# doodle_with_clock3_jump5.net
KiCad netlist of a schematic drawn in EAGLE
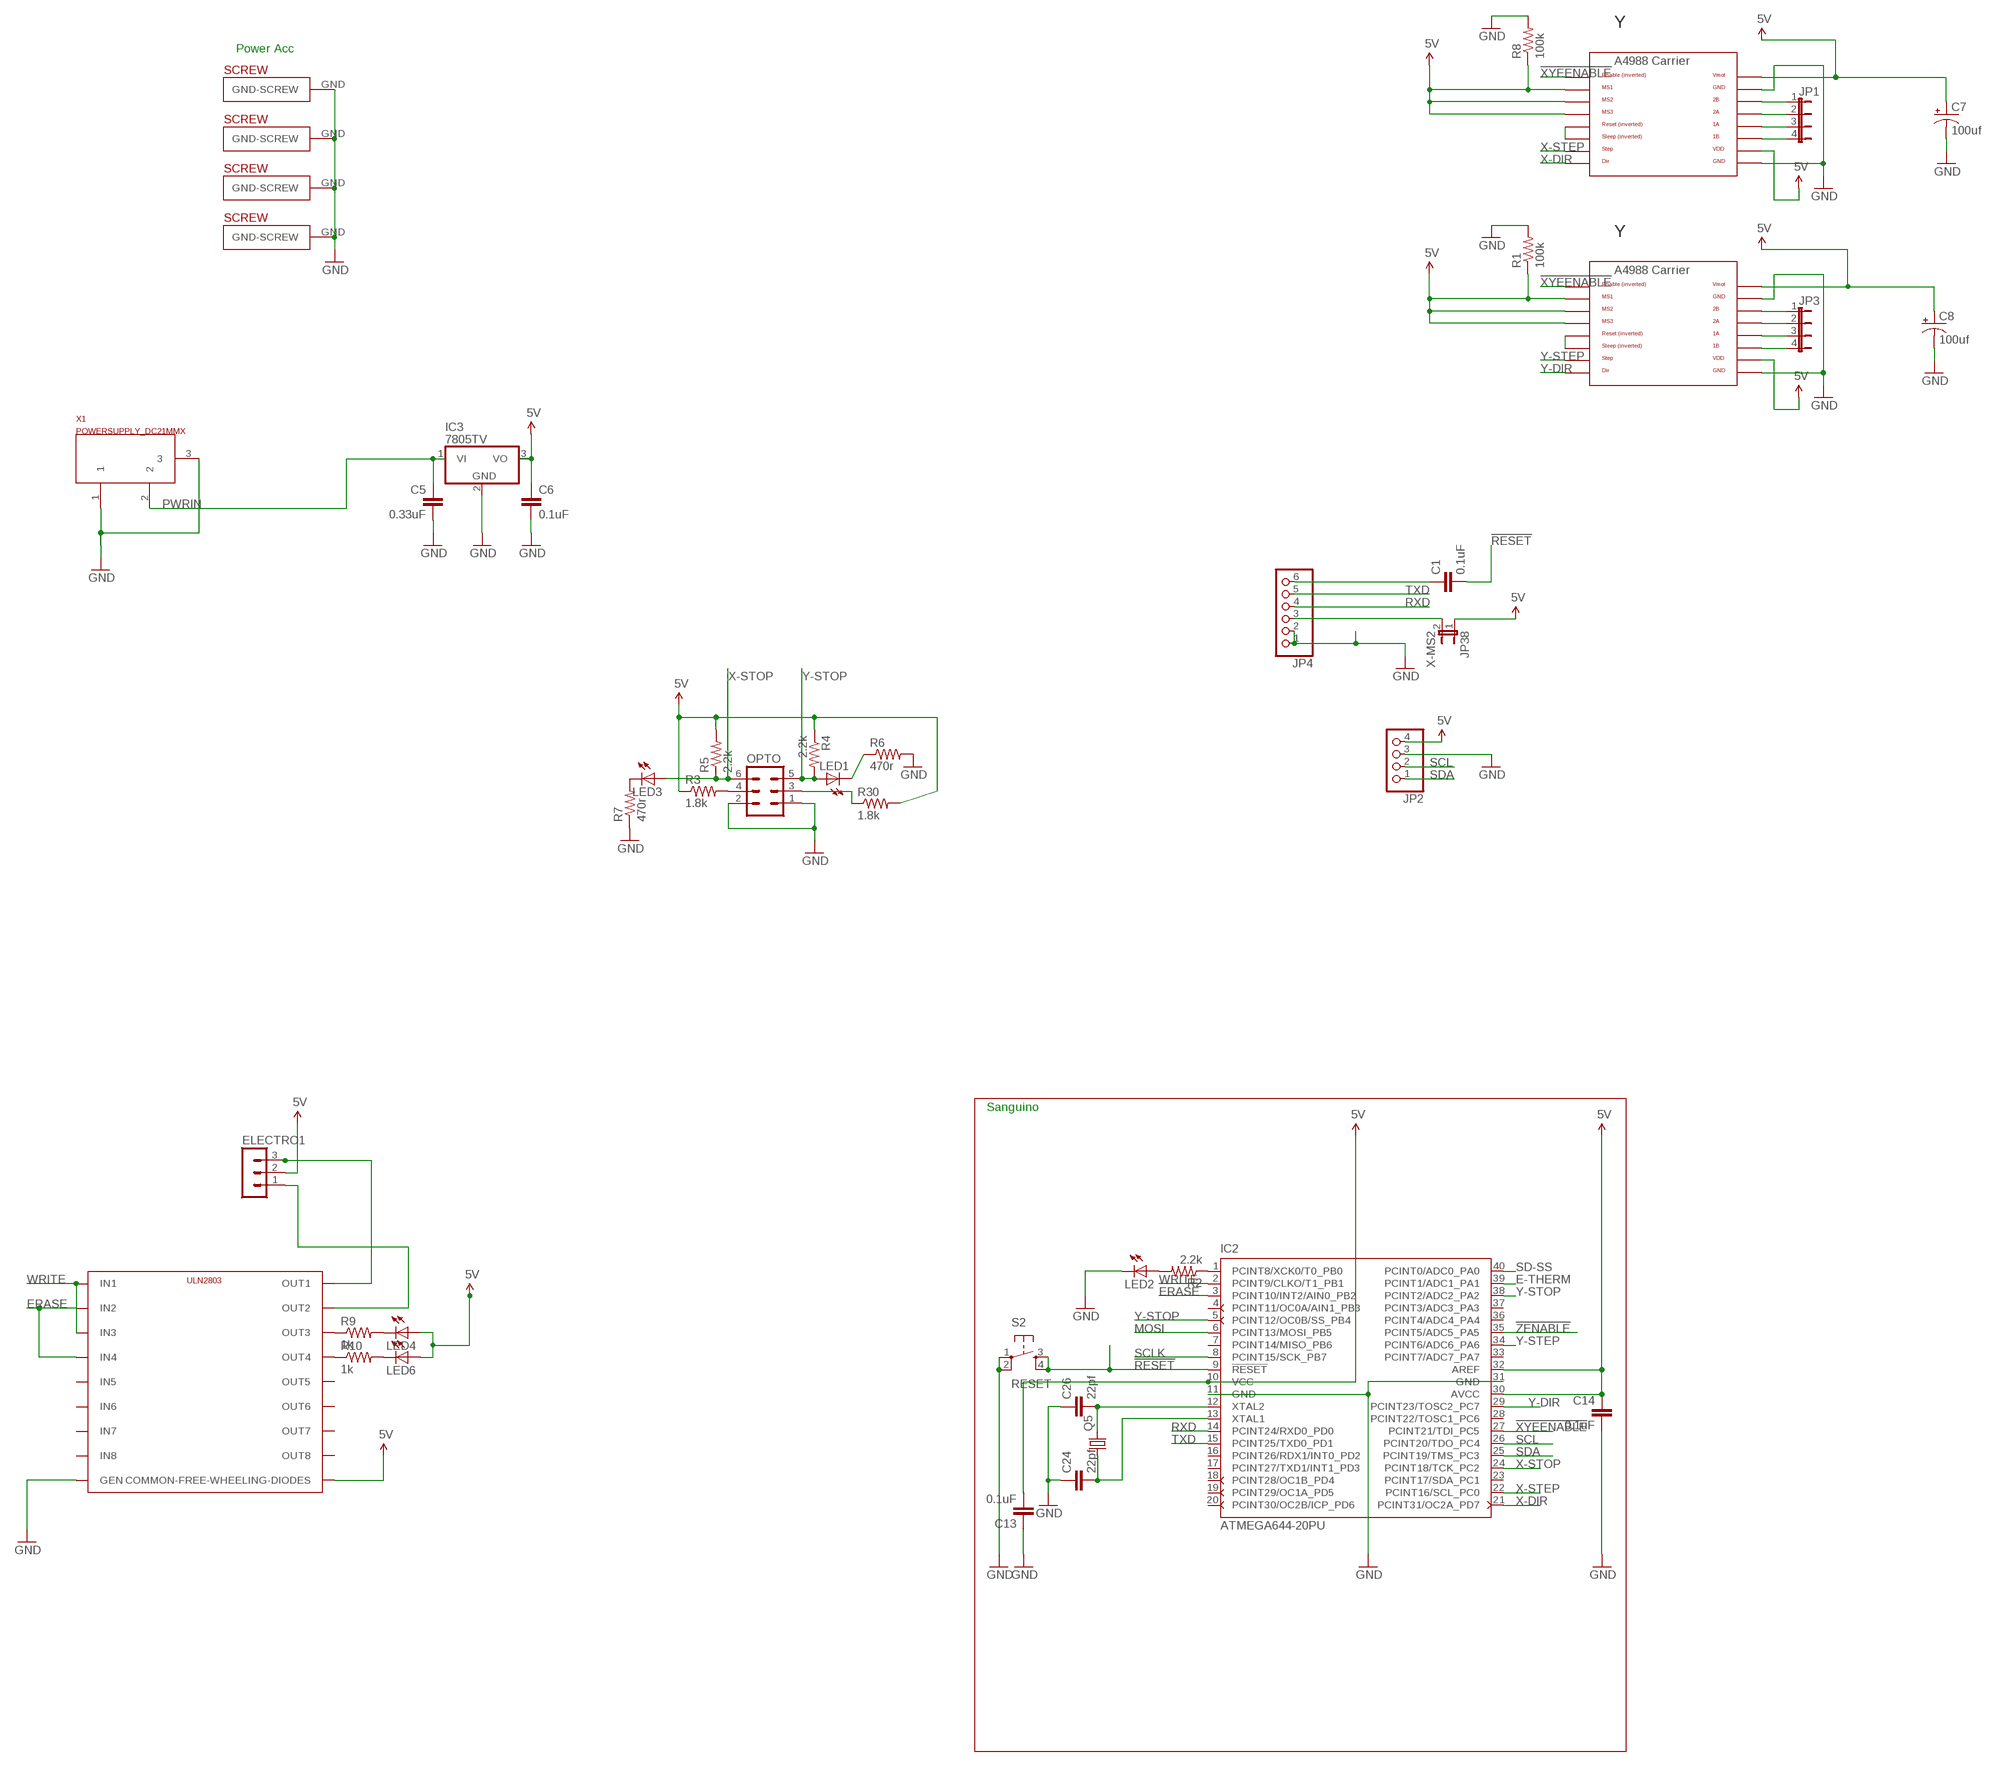
[diagram p0: schematic, sheet 1]

(export (version "E")
  (design (tool "Eeschema 10.0.6"))
  (components
    (comp (ref "C1")
      (value "0.1uF")
      (footprint "eagle-import:CAP-PTH-SMALL2")
      (libsource (lib "eagle-import") (part "CAPPTH2"))
    )
    (comp (ref "C5")
      (value "0.33uF")
      (footprint "eagle-import:CAP-PTH-SMALL2")
      (libsource (lib "eagle-import") (part "CAPPTH2"))
    )
    (comp (ref "C6")
      (value "0.1uF")
      (footprint "eagle-import:CAP-PTH-SMALL2")
      (libsource (lib "eagle-import") (part "CAPPTH2"))
    )
    (comp (ref "C7")
      (value "100uf")
      (footprint "eagle-import:CPOL-RADIAL-100UF-25V")
      (libsource (lib "eagle-import") (part "CAP_POLPTH1"))
    )
    (comp (ref "C8")
      (value "100uf")
      (footprint "eagle-import:CPOL-RADIAL-100UF-25V")
      (libsource (lib "eagle-import") (part "CAP_POLPTH1"))
    )
    (comp (ref "C13")
      (value "0.1uF")
      (footprint "eagle-import:CAP-PTH-SMALL2")
      (libsource (lib "eagle-import") (part "CAPPTH2"))
    )
    (comp (ref "C14")
      (value "0.1uF")
      (footprint "eagle-import:CAP-PTH-SMALL2")
      (libsource (lib "eagle-import") (part "CAPPTH2"))
    )
    (comp (ref "C24")
      (value "22pf")
      (footprint "eagle-import:CAP-PTH-SMALL2")
      (libsource (lib "eagle-import") (part "CAPPTH2"))
    )
    (comp (ref "C26")
      (value "22pf")
      (footprint "eagle-import:CAP-PTH-SMALL2")
      (libsource (lib "eagle-import") (part "CAPPTH2"))
    )
    (comp (ref "ELECTRO1")
      (value "MA03-1")
      (footprint "eagle-import:MA03-1")
      (libsource (lib "eagle-import") (part "MA03-1"))
    )
    (comp (ref "IC2")
      (value "ATMEGA644-20PU")
      (footprint "eagle-import:DIL40")
      (libsource (lib "eagle-import") (part "ATMEGA644-PU20"))
    )
    (comp (ref "IC3")
      (value "7805TV")
      (footprint "eagle-import:TO220V")
      (libsource (lib "eagle-import") (part "78TV05"))
    )
    (comp (ref "JP1")
      (value "JP4E")
      (footprint "eagle-import:JP4")
      (libsource (lib "eagle-import") (part "JP4E"))
    )
    (comp (ref "JP2")
      (value "PINHD-1X4")
      (footprint "eagle-import:1X04")
      (libsource (lib "eagle-import") (part "PINHD-1X4"))
    )
    (comp (ref "JP3")
      (value "JP4E")
      (footprint "eagle-import:JP4")
      (libsource (lib "eagle-import") (part "JP4E"))
    )
    (comp (ref "JP4")
      (value "PINHD-1X6/90")
      (footprint "eagle-import:1X06_90")
      (libsource (lib "eagle-import") (part "PINHD-1X6/90"))
    )
    (comp (ref "JP38")
      (value "X-MS2")
      (footprint "eagle-import:1X02")
      (libsource (lib "eagle-import") (part "JUMPER-2PTH"))
    )
    (comp (ref "LED1")
      (value "LED3MM")
      (footprint "eagle-import:LED3MM")
      (libsource (lib "eagle-import") (part "LED3MM"))
    )
    (comp (ref "LED2")
      (value "LED3MM")
      (footprint "eagle-import:LED3MM")
      (libsource (lib "eagle-import") (part "LED3MM"))
    )
    (comp (ref "LED3")
      (value "LED3MM")
      (footprint "eagle-import:LED3MM")
      (libsource (lib "eagle-import") (part "LED3MM"))
    )
    (comp (ref "LED4")
      (value "LED3MM")
      (footprint "eagle-import:LED3MM")
      (libsource (lib "eagle-import") (part "LED3MM"))
    )
    (comp (ref "LED6")
      (value "LED3MM")
      (footprint "eagle-import:LED3MM")
      (libsource (lib "eagle-import") (part "LED3MM"))
    )
    (comp (ref "OPTO")
      (value "MA03-2")
      (footprint "eagle-import:MA03-2")
      (libsource (lib "eagle-import") (part "MA03-2"))
    )
    (comp (ref "Q5")
      (value "CRYSTALHC49S")
      (footprint "eagle-import:HC49_S")
      (libsource (lib "eagle-import") (part "CRYSTALHC49S"))
    )
    (comp (ref "R1")
      (value "100k")
      (footprint "eagle-import:0207_7")
      (libsource (lib "eagle-import") (part "R-US_0207/7"))
    )
    (comp (ref "R2")
      (value "2.2k")
      (footprint "eagle-import:0207_2V")
      (libsource (lib "eagle-import") (part "resistor_R-US_0207/2V"))
    )
    (comp (ref "R3")
      (value "1.8k")
      (footprint "eagle-import:0207_2V")
      (libsource (lib "eagle-import") (part "resistor_R-US_0207/2V"))
    )
    (comp (ref "R4")
      (value "2.2k")
      (footprint "eagle-import:0207_2V")
      (libsource (lib "eagle-import") (part "resistor_R-US_0207/2V"))
    )
    (comp (ref "R5")
      (value "2.2k")
      (footprint "eagle-import:0207_2V")
      (libsource (lib "eagle-import") (part "resistor_R-US_0207/2V"))
    )
    (comp (ref "R6")
      (value "470r")
      (footprint "eagle-import:0207_2V")
      (libsource (lib "eagle-import") (part "resistor_R-US_0207/2V"))
    )
    (comp (ref "R7")
      (value "470r")
      (footprint "eagle-import:0207_2V")
      (libsource (lib "eagle-import") (part "resistor_R-US_0207/2V"))
    )
    (comp (ref "R8")
      (value "100k")
      (footprint "eagle-import:0207_7")
      (libsource (lib "eagle-import") (part "R-US_0207/7"))
    )
    (comp (ref "R9")
      (value "1k")
      (footprint "eagle-import:0207_2V")
      (libsource (lib "eagle-import") (part "resistor_R-US_0207/2V"))
    )
    (comp (ref "R10")
      (value "1k")
      (footprint "eagle-import:0207_2V")
      (libsource (lib "eagle-import") (part "resistor_R-US_0207/2V"))
    )
    (comp (ref "R30")
      (value "1.8k")
      (footprint "eagle-import:0207_2V")
      (libsource (lib "eagle-import") (part "resistor_R-US_0207/2V"))
    )
    (comp (ref "S2")
      (value "RESET")
      (footprint "eagle-import:TACTILE-PTH")
      (libsource (lib "eagle-import") (part "TAC_SWITCHPTH"))
    )
    (comp (ref "U$1")
      (value "A4988BREAKOUT")
      (footprint "eagle-import:A4988BREAKOUT")
      (libsource (lib "eagle-import") (part "A4988BREAKOUT"))
    )
    (comp (ref "U$2")
      (value "ULN2803")
      (footprint "eagle-import:P-DIP")
      (libsource (lib "eagle-import") (part "ULN2803"))
    )
    (comp (ref "U$7")
      (value "A4988BREAKOUT")
      (footprint "eagle-import:A4988BREAKOUT")
      (libsource (lib "eagle-import") (part "A4988BREAKOUT"))
    )
    (comp (ref "U$14")
      (value "PLATED-SCREW")
      (footprint "eagle-import:PLATEDSCREW")
      (libsource (lib "eagle-import") (part "PLATED-SCREW"))
    )
    (comp (ref "U$17")
      (value "PLATED-SCREW")
      (footprint "eagle-import:PLATEDSCREW")
      (libsource (lib "eagle-import") (part "PLATED-SCREW"))
    )
    (comp (ref "U$18")
      (value "PLATED-SCREW")
      (footprint "eagle-import:PLATEDSCREW")
      (libsource (lib "eagle-import") (part "PLATED-SCREW"))
    )
    (comp (ref "U$38")
      (value "PLATED-SCREW")
      (footprint "eagle-import:PLATEDSCREW")
      (libsource (lib "eagle-import") (part "PLATED-SCREW"))
    )
    (comp (ref "X1")
      (value "POWERSUPPLY_DC21MMX")
      (footprint "eagle-import:POWERSUPPLY_DC-21MM")
      (libsource (lib "eagle-import") (part "POWERSUPPLY_DC21MMX"))
    )
  )
  (nets
    (net (code "1") (name "/E-THERM") (class "Default")
      (node (ref "IC2") (pin "39") (pinfunction "PCINT1/ADC1_PA1_39") (pintype "bidirectional"))
    )
    (net (code "2") (name "/ERASE") (class "Default")
      (node (ref "IC2") (pin "3") (pinfunction "PCINT10/INT2/AIN0_PB2_3") (pintype "bidirectional"))
      (node (ref "U$2") (pin "IN2") (pinfunction "IN2_IN2") (pintype "input"))
      (node (ref "U$2") (pin "IN4") (pinfunction "IN4_IN4") (pintype "input"))
    )
    (net (code "3") (name "/MOSI") (class "Default")
      (node (ref "IC2") (pin "6") (pinfunction "PCINT13/MOSI_PB5_6") (pintype "bidirectional"))
    )
    (net (code "4") (name "/PWRIN") (class "Default")
      (node (ref "C5") (pin "1") (pinfunction "1_1") (pintype "passive"))
      (node (ref "IC3") (pin "1") (pinfunction "VI_1") (pintype "input"))
      (node (ref "X1") (pin "2") (pinfunction "2_2") (pintype "power_in"))
    )
    (net (code "5") (name "/RXD") (class "Default")
      (node (ref "IC2") (pin "14") (pinfunction "PCINT24/RXD0_PD0_14") (pintype "bidirectional"))
      (node (ref "JP4") (pin "4") (pinfunction "4_4") (pintype "passive"))
    )
    (net (code "6") (name "/SCL") (class "Default")
      (node (ref "IC2") (pin "26") (pinfunction "PCINT20/TDO_PC4_26") (pintype "bidirectional"))
      (node (ref "JP2") (pin "2") (pinfunction "2_2") (pintype "passive"))
    )
    (net (code "7") (name "/SCLK") (class "Default")
      (node (ref "IC2") (pin "8") (pinfunction "PCINT15/SCK_PB7_8") (pintype "bidirectional"))
    )
    (net (code "8") (name "/SD-SS") (class "Default")
      (node (ref "IC2") (pin "40") (pinfunction "PCINT0/ADC0_PA0_40") (pintype "bidirectional"))
    )
    (net (code "9") (name "/SDA") (class "Default")
      (node (ref "IC2") (pin "25") (pinfunction "PCINT19/TMS_PC3_25") (pintype "bidirectional"))
      (node (ref "JP2") (pin "1") (pinfunction "1_1") (pintype "passive"))
    )
    (net (code "10") (name "/TXD") (class "Default")
      (node (ref "IC2") (pin "15") (pinfunction "PCINT25/TXD0_PD1_15") (pintype "bidirectional"))
      (node (ref "JP4") (pin "5") (pinfunction "5_5") (pintype "passive"))
    )
    (net (code "11") (name "/WRITE") (class "Default")
      (node (ref "IC2") (pin "2") (pinfunction "PCINT9/CLKO/T1_PB1_2") (pintype "bidirectional"))
      (node (ref "U$2") (pin "IN1") (pinfunction "IN1_IN1") (pintype "input"))
      (node (ref "U$2") (pin "IN3") (pinfunction "IN3_IN3") (pintype "input"))
    )
    (net (code "12") (name "/X-DIR") (class "Default")
      (node (ref "IC2") (pin "21") (pinfunction "PCINT31/OC2A_PD7_21") (pintype "bidirectional"))
      (node (ref "U$7") (pin "DIR") (pinfunction "DIR_DIR") (pintype "input"))
    )
    (net (code "13") (name "/X-STEP") (class "Default")
      (node (ref "IC2") (pin "22") (pinfunction "PCINT16/SCL_PC0_22") (pintype "bidirectional"))
      (node (ref "U$7") (pin "STEP") (pinfunction "STEP_STEP") (pintype "input"))
    )
    (net (code "14") (name "/X-STOP") (class "Default")
      (node (ref "IC2") (pin "24") (pinfunction "PCINT18/TCK_PC2_24") (pintype "bidirectional"))
      (node (ref "LED3") (pin "A") (pinfunction "A_A") (pintype "passive"))
      (node (ref "OPTO") (pin "6") (pinfunction "6_6") (pintype "passive"))
      (node (ref "R5") (pin "1") (pinfunction "1_1") (pintype "passive"))
    )
    (net (code "15") (name "/Y-DIR") (class "Default")
      (node (ref "IC2") (pin "29") (pinfunction "PCINT23/TOSC2_PC7_29") (pintype "bidirectional"))
      (node (ref "U$1") (pin "DIR") (pinfunction "DIR_DIR") (pintype "input"))
    )
    (net (code "16") (name "/Y-STEP") (class "Default")
      (node (ref "IC2") (pin "34") (pinfunction "PCINT6/ADC6_PA6_34") (pintype "bidirectional"))
      (node (ref "U$1") (pin "STEP") (pinfunction "STEP_STEP") (pintype "input"))
    )
    (net (code "17") (name "/Y-STOP") (class "Default")
      (node (ref "IC2") (pin "38") (pinfunction "PCINT2/ADC2_PA2_38") (pintype "bidirectional"))
      (node (ref "IC2") (pin "5") (pinfunction "PCINT12/OC0B/SS_PB4_5") (pintype "bidirectional"))
      (node (ref "LED1") (pin "A") (pinfunction "A_A") (pintype "passive"))
      (node (ref "OPTO") (pin "5") (pinfunction "5_5") (pintype "passive"))
      (node (ref "R4") (pin "2") (pinfunction "2_2") (pintype "passive"))
    )
    (net (code "18") (name "/~{RESET}") (class "Default")
      (node (ref "C1") (pin "2") (pinfunction "2_2") (pintype "passive"))
      (node (ref "IC2") (pin "9") (pinfunction "~{RESET}_9") (pintype "input"))
      (node (ref "S2") (pin "3") (pinfunction "3_3") (pintype "passive"))
      (node (ref "S2") (pin "4") (pinfunction "4_4") (pintype "passive"))
    )
    (net (code "19") (name "/~{XYEENABLE}") (class "Default")
      (node (ref "IC2") (pin "27") (pinfunction "PCINT21/TDI_PC5_27") (pintype "bidirectional"))
      (node (ref "U$1") (pin "EN") (pinfunction "EN_EN") (pintype "input"))
      (node (ref "U$7") (pin "EN") (pinfunction "EN_EN") (pintype "input"))
    )
    (net (code "20") (name "/~{ZENABLE}") (class "Default")
      (node (ref "IC2") (pin "35") (pinfunction "PCINT5/ADC5_PA5_35") (pintype "bidirectional"))
    )
    (net (code "21") (name "5V") (class "Default")
      (node (ref "C13") (pin "2") (pinfunction "2_2") (pintype "passive"))
      (node (ref "C14") (pin "1") (pinfunction "1_1") (pintype "passive"))
      (node (ref "C6") (pin "1") (pinfunction "1_1") (pintype "passive"))
      (node (ref "C7") (pin "1") (pinfunction "+_1") (pintype "passive"))
      (node (ref "C8") (pin "1") (pinfunction "+_1") (pintype "passive"))
      (node (ref "ELECTRO1") (pin "2") (pinfunction "2_2") (pintype "passive"))
      (node (ref "IC2") (pin "10") (pinfunction "VCC_10") (pintype "power_in"))
      (node (ref "IC2") (pin "30") (pinfunction "AVCC_30") (pintype "power_in"))
      (node (ref "IC2") (pin "32") (pinfunction "AREF_32") (pintype "passive"))
      (node (ref "IC3") (pin "3") (pinfunction "VO_3") (pintype "passive"))
      (node (ref "JP2") (pin "4") (pinfunction "4_4") (pintype "passive"))
      (node (ref "JP38") (pin "1") (pinfunction "1_1") (pintype "passive"))
      (node (ref "LED4") (pin "A") (pinfunction "A_A") (pintype "passive"))
      (node (ref "LED6") (pin "A") (pinfunction "A_A") (pintype "passive"))
      (node (ref "R1") (pin "1") (pinfunction "1_1") (pintype "passive"))
      (node (ref "R3") (pin "1") (pinfunction "1_1") (pintype "passive"))
      (node (ref "R30") (pin "2") (pinfunction "2_2") (pintype "passive"))
      (node (ref "R4") (pin "1") (pinfunction "1_1") (pintype "passive"))
      (node (ref "R5") (pin "2") (pinfunction "2_2") (pintype "passive"))
      (node (ref "R8") (pin "1") (pinfunction "1_1") (pintype "passive"))
      (node (ref "U$1") (pin "MS1") (pinfunction "MS1_MS1") (pintype "input"))
      (node (ref "U$1") (pin "MS2") (pinfunction "MS2_MS2") (pintype "input"))
      (node (ref "U$1") (pin "MS3") (pinfunction "MS3_MS3") (pintype "input"))
      (node (ref "U$1") (pin "VDD") (pinfunction "VDD_VDD") (pintype "power_in"))
      (node (ref "U$1") (pin "VMOT") (pinfunction "VMOT_VMOT") (pintype "power_in"))
      (node (ref "U$2") (pin "COMMON-FREE-WHEELING-DIODES") (pinfunction "COMMON-FREE-WHEELING-DIODES_COMMON-FREE-WHEELING-DIODES") (pintype "output"))
      (node (ref "U$7") (pin "MS1") (pinfunction "MS1_MS1") (pintype "input"))
      (node (ref "U$7") (pin "MS2") (pinfunction "MS2_MS2") (pintype "input"))
      (node (ref "U$7") (pin "MS3") (pinfunction "MS3_MS3") (pintype "input"))
      (node (ref "U$7") (pin "VDD") (pinfunction "VDD_VDD") (pintype "power_in"))
      (node (ref "U$7") (pin "VMOT") (pinfunction "VMOT_VMOT") (pintype "power_in"))
    )
    (net (code "22") (name "GND") (class "Default")
      (node (ref "C13") (pin "1") (pinfunction "1_1") (pintype "passive"))
      (node (ref "C14") (pin "2") (pinfunction "2_2") (pintype "passive"))
      (node (ref "C24") (pin "1") (pinfunction "1_1") (pintype "passive"))
      (node (ref "C26") (pin "1") (pinfunction "1_1") (pintype "passive"))
      (node (ref "C5") (pin "2") (pinfunction "2_2") (pintype "passive"))
      (node (ref "C6") (pin "2") (pinfunction "2_2") (pintype "passive"))
      (node (ref "C7") (pin "2") (pinfunction "-_2") (pintype "passive"))
      (node (ref "C8") (pin "2") (pinfunction "-_2") (pintype "passive"))
      (node (ref "IC2") (pin "11") (pinfunction "GND_11") (pintype "power_in"))
      (node (ref "IC2") (pin "31") (pinfunction "GND_31") (pintype "power_in"))
      (node (ref "IC3") (pin "2") (pinfunction "GND_2") (pintype "passive"))
      (node (ref "JP2") (pin "3") (pinfunction "3_3") (pintype "passive"))
      (node (ref "JP4") (pin "1") (pinfunction "1_1") (pintype "passive"))
      (node (ref "JP4") (pin "2") (pinfunction "2_2") (pintype "passive"))
      (node (ref "LED2") (pin "K") (pinfunction "C_K") (pintype "passive"))
      (node (ref "OPTO") (pin "1") (pinfunction "1_1") (pintype "passive"))
      (node (ref "OPTO") (pin "2") (pinfunction "2_2") (pintype "passive"))
      (node (ref "R1") (pin "2") (pinfunction "2_2") (pintype "passive"))
      (node (ref "R6") (pin "2") (pinfunction "2_2") (pintype "passive"))
      (node (ref "R7") (pin "1") (pinfunction "1_1") (pintype "passive"))
      (node (ref "R8") (pin "2") (pinfunction "2_2") (pintype "passive"))
      (node (ref "S2") (pin "1") (pinfunction "1_1") (pintype "passive"))
      (node (ref "S2") (pin "2") (pinfunction "2_2") (pintype "passive"))
      (node (ref "U$1") (pin "GND") (pinfunction "GND_GND") (pintype "power_in"))
      (node (ref "U$1") (pin "GND@0") (pinfunction "GND_GND@0") (pintype "power_in"))
      (node (ref "U$14") (pin "GND") (pinfunction "GND-SCREW_GND") (pintype "bidirectional"))
      (node (ref "U$17") (pin "GND") (pinfunction "GND-SCREW_GND") (pintype "bidirectional"))
      (node (ref "U$18") (pin "GND") (pinfunction "GND-SCREW_GND") (pintype "bidirectional"))
      (node (ref "U$2") (pin "GEN") (pinfunction "GEN_GEN") (pintype "power_in"))
      (node (ref "U$38") (pin "GND") (pinfunction "GND-SCREW_GND") (pintype "bidirectional"))
      (node (ref "U$7") (pin "GND") (pinfunction "GND_GND") (pintype "power_in"))
      (node (ref "U$7") (pin "GND@0") (pinfunction "GND_GND@0") (pintype "power_in"))
      (node (ref "X1") (pin "1") (pinfunction "1_1") (pintype "power_in"))
      (node (ref "X1") (pin "3") (pinfunction "3_3") (pintype "power_in"))
    )
    (net (code "23") (name "Net-(C1-Pad1)") (class "Default")
      (node (ref "C1") (pin "1") (pinfunction "1_1") (pintype "passive"))
      (node (ref "JP4") (pin "6") (pinfunction "6_6") (pintype "passive"))
    )
    (net (code "24") (name "Net-(ELECTRO1-Pad1)") (class "Default")
      (node (ref "ELECTRO1") (pin "1") (pinfunction "1_1") (pintype "passive"))
      (node (ref "U$2") (pin "OUT2") (pinfunction "OUT2_OUT2") (pintype "output"))
    )
    (net (code "25") (name "Net-(ELECTRO1-Pad3)") (class "Default")
      (node (ref "ELECTRO1") (pin "3") (pinfunction "3_3") (pintype "passive"))
      (node (ref "U$2") (pin "OUT1") (pinfunction "OUT1_OUT1") (pintype "output"))
    )
    (net (code "26") (name "Net-(IC2-PCINT8{slash}XCK0{slash}T0_PB0)") (class "Default")
      (node (ref "IC2") (pin "1") (pinfunction "PCINT8/XCK0/T0_PB0_1") (pintype "bidirectional"))
      (node (ref "R2") (pin "1") (pinfunction "1_1") (pintype "passive"))
    )
    (net (code "27") (name "Net-(IC2-XTAL1)") (class "Default")
      (node (ref "C24") (pin "2") (pinfunction "2_2") (pintype "passive"))
      (node (ref "IC2") (pin "13") (pinfunction "XTAL1_13") (pintype "input"))
      (node (ref "Q5") (pin "1") (pinfunction "1_1") (pintype "passive"))
    )
    (net (code "28") (name "Net-(IC2-XTAL2)") (class "Default")
      (node (ref "C26") (pin "2") (pinfunction "2_2") (pintype "passive"))
      (node (ref "IC2") (pin "12") (pinfunction "XTAL2_12") (pintype "output"))
      (node (ref "Q5") (pin "2") (pinfunction "2_2") (pintype "passive"))
    )
    (net (code "29") (name "Net-(JP1-Pad1)") (class "Default")
      (node (ref "JP1") (pin "1") (pinfunction "1_1") (pintype "passive"))
      (node (ref "U$7") (pin "2B") (pinfunction "2B_2B") (pintype "output"))
    )
    (net (code "30") (name "Net-(JP1-Pad2)") (class "Default")
      (node (ref "JP1") (pin "2") (pinfunction "2_2") (pintype "passive"))
      (node (ref "U$7") (pin "2A") (pinfunction "2A_2A") (pintype "output"))
    )
    (net (code "31") (name "Net-(JP1-Pad3)") (class "Default")
      (node (ref "JP1") (pin "3") (pinfunction "3_3") (pintype "passive"))
      (node (ref "U$7") (pin "1A") (pinfunction "1A_1A") (pintype "output"))
    )
    (net (code "32") (name "Net-(JP1-Pad4)") (class "Default")
      (node (ref "JP1") (pin "4") (pinfunction "4_4") (pintype "passive"))
      (node (ref "U$7") (pin "1B") (pinfunction "1B_1B") (pintype "output"))
    )
    (net (code "33") (name "Net-(JP3-Pad1)") (class "Default")
      (node (ref "JP3") (pin "1") (pinfunction "1_1") (pintype "passive"))
      (node (ref "U$1") (pin "2B") (pinfunction "2B_2B") (pintype "output"))
    )
    (net (code "34") (name "Net-(JP3-Pad2)") (class "Default")
      (node (ref "JP3") (pin "2") (pinfunction "2_2") (pintype "passive"))
      (node (ref "U$1") (pin "2A") (pinfunction "2A_2A") (pintype "output"))
    )
    (net (code "35") (name "Net-(JP3-Pad3)") (class "Default")
      (node (ref "JP3") (pin "3") (pinfunction "3_3") (pintype "passive"))
      (node (ref "U$1") (pin "1A") (pinfunction "1A_1A") (pintype "output"))
    )
    (net (code "36") (name "Net-(JP3-Pad4)") (class "Default")
      (node (ref "JP3") (pin "4") (pinfunction "4_4") (pintype "passive"))
      (node (ref "U$1") (pin "1B") (pinfunction "1B_1B") (pintype "output"))
    )
    (net (code "37") (name "Net-(JP38-Pad2)") (class "Default")
      (node (ref "JP38") (pin "2") (pinfunction "2_2") (pintype "passive"))
      (node (ref "JP4") (pin "3") (pinfunction "3_3") (pintype "passive"))
    )
    (net (code "38") (name "Net-(LED1-C)") (class "Default")
      (node (ref "LED1") (pin "K") (pinfunction "C_K") (pintype "passive"))
      (node (ref "R6") (pin "1") (pinfunction "1_1") (pintype "passive"))
    )
    (net (code "39") (name "Net-(LED2-PadA)") (class "Default")
      (node (ref "LED2") (pin "A") (pinfunction "A_A") (pintype "passive"))
      (node (ref "R2") (pin "2") (pinfunction "2_2") (pintype "passive"))
    )
    (net (code "40") (name "Net-(LED3-C)") (class "Default")
      (node (ref "LED3") (pin "K") (pinfunction "C_K") (pintype "passive"))
      (node (ref "R7") (pin "2") (pinfunction "2_2") (pintype "passive"))
    )
    (net (code "41") (name "Net-(LED4-C)") (class "Default")
      (node (ref "LED4") (pin "K") (pinfunction "C_K") (pintype "passive"))
      (node (ref "R9") (pin "2") (pinfunction "2_2") (pintype "passive"))
    )
    (net (code "42") (name "Net-(LED6-C)") (class "Default")
      (node (ref "LED6") (pin "K") (pinfunction "C_K") (pintype "passive"))
      (node (ref "R10") (pin "2") (pinfunction "2_2") (pintype "passive"))
    )
    (net (code "43") (name "Net-(OPTO-Pad3)") (class "Default")
      (node (ref "OPTO") (pin "3") (pinfunction "3_3") (pintype "passive"))
      (node (ref "R30") (pin "1") (pinfunction "1_1") (pintype "passive"))
    )
    (net (code "44") (name "Net-(OPTO-Pad4)") (class "Default")
      (node (ref "OPTO") (pin "4") (pinfunction "4_4") (pintype "passive"))
      (node (ref "R3") (pin "2") (pinfunction "2_2") (pintype "passive"))
    )
    (net (code "45") (name "Net-(R9-Pad1)") (class "Default")
      (node (ref "R9") (pin "1") (pinfunction "1_1") (pintype "passive"))
      (node (ref "U$2") (pin "OUT3") (pinfunction "OUT3_OUT3") (pintype "output"))
    )
    (net (code "46") (name "Net-(R10-Pad1)") (class "Default")
      (node (ref "R10") (pin "1") (pinfunction "1_1") (pintype "passive"))
      (node (ref "U$2") (pin "OUT4") (pinfunction "OUT4_OUT4") (pintype "output"))
    )
    (net (code "47") (name "Net-(U$1-SLEEP)") (class "Default")
      (node (ref "U$1") (pin "RST") (pinfunction "RST_RST") (pintype "input"))
      (node (ref "U$1") (pin "SLP") (pinfunction "SLEEP_SLP") (pintype "input"))
    )
    (net (code "48") (name "Net-(U$7-SLEEP)") (class "Default")
      (node (ref "U$7") (pin "RST") (pinfunction "RST_RST") (pintype "input"))
      (node (ref "U$7") (pin "SLP") (pinfunction "SLEEP_SLP") (pintype "input"))
    )
    (net (code "49") (name "unconnected-(IC2-PCINT3{slash}ADC3_PA3-Pad37)") (class "Default")
      (node (ref "IC2") (pin "37") (pinfunction "PCINT3/ADC3_PA3_37") (pintype "bidirectional"))
    )
    (net (code "50") (name "unconnected-(IC2-PCINT4{slash}ADC4_PA4-Pad36)") (class "Default")
      (node (ref "IC2") (pin "36") (pinfunction "PCINT4/ADC4_PA4_36") (pintype "bidirectional"))
    )
    (net (code "51") (name "unconnected-(IC2-PCINT7{slash}ADC7_PA7-Pad33)") (class "Default")
      (node (ref "IC2") (pin "33") (pinfunction "PCINT7/ADC7_PA7_33") (pintype "bidirectional"))
    )
    (net (code "52") (name "unconnected-(IC2-PCINT11{slash}OC0A{slash}AIN1_PB3-Pad4)") (class "Default")
      (node (ref "IC2") (pin "4") (pinfunction "PCINT11/OC0A/AIN1_PB3_4") (pintype "bidirectional"))
    )
    (net (code "53") (name "unconnected-(IC2-PCINT14{slash}MISO_PB6-Pad7)") (class "Default")
      (node (ref "IC2") (pin "7") (pinfunction "PCINT14/MISO_PB6_7") (pintype "bidirectional"))
    )
    (net (code "54") (name "unconnected-(IC2-PCINT17{slash}SDA_PC1-Pad23)") (class "Default")
      (node (ref "IC2") (pin "23") (pinfunction "PCINT17/SDA_PC1_23") (pintype "bidirectional"))
    )
    (net (code "55") (name "unconnected-(IC2-PCINT22{slash}TOSC1_PC6-Pad28)") (class "Default")
      (node (ref "IC2") (pin "28") (pinfunction "PCINT22/TOSC1_PC6_28") (pintype "bidirectional"))
    )
    (net (code "56") (name "unconnected-(IC2-PCINT26{slash}RDX1{slash}INT0_PD2-Pad16)") (class "Default")
      (node (ref "IC2") (pin "16") (pinfunction "PCINT26/RDX1/INT0_PD2_16") (pintype "bidirectional"))
    )
    (net (code "57") (name "unconnected-(IC2-PCINT27{slash}TXD1{slash}INT1_PD3-Pad17)") (class "Default")
      (node (ref "IC2") (pin "17") (pinfunction "PCINT27/TXD1/INT1_PD3_17") (pintype "bidirectional"))
    )
    (net (code "58") (name "unconnected-(IC2-PCINT28{slash}OC1B_PD4-Pad18)") (class "Default")
      (node (ref "IC2") (pin "18") (pinfunction "PCINT28/OC1B_PD4_18") (pintype "bidirectional"))
    )
    (net (code "59") (name "unconnected-(IC2-PCINT29{slash}OC1A_PD5-Pad19)") (class "Default")
      (node (ref "IC2") (pin "19") (pinfunction "PCINT29/OC1A_PD5_19") (pintype "bidirectional"))
    )
    (net (code "60") (name "unconnected-(IC2-PCINT30{slash}OC2B{slash}ICP_PD6-Pad20)") (class "Default")
      (node (ref "IC2") (pin "20") (pinfunction "PCINT30/OC2B/ICP_PD6_20") (pintype "bidirectional"))
    )
    (net (code "61") (name "unconnected-(U$2-PadIN5)") (class "Default")
      (node (ref "U$2") (pin "IN5") (pinfunction "IN5_IN5") (pintype "input"))
    )
    (net (code "62") (name "unconnected-(U$2-PadIN6)") (class "Default")
      (node (ref "U$2") (pin "IN6") (pinfunction "IN6_IN6") (pintype "input"))
    )
    (net (code "63") (name "unconnected-(U$2-PadIN7)") (class "Default")
      (node (ref "U$2") (pin "IN7") (pinfunction "IN7_IN7") (pintype "input"))
    )
    (net (code "64") (name "unconnected-(U$2-PadIN8)") (class "Default")
      (node (ref "U$2") (pin "IN8") (pinfunction "IN8_IN8") (pintype "input"))
    )
    (net (code "65") (name "unconnected-(U$2-PadOUT5)") (class "Default")
      (node (ref "U$2") (pin "OUT5") (pinfunction "OUT5_OUT5") (pintype "output"))
    )
    (net (code "66") (name "unconnected-(U$2-PadOUT6)") (class "Default")
      (node (ref "U$2") (pin "OUT6") (pinfunction "OUT6_OUT6") (pintype "output"))
    )
    (net (code "67") (name "unconnected-(U$2-PadOUT7)") (class "Default")
      (node (ref "U$2") (pin "OUT7") (pinfunction "OUT7_OUT7") (pintype "output"))
    )
    (net (code "68") (name "unconnected-(U$2-PadOUT8)") (class "Default")
      (node (ref "U$2") (pin "OUT8") (pinfunction "OUT8_OUT8") (pintype "output"))
    )
  )
)
